# rf_router_swrmet.net
KiCad netlist of a schematic drawn in Altium Designer
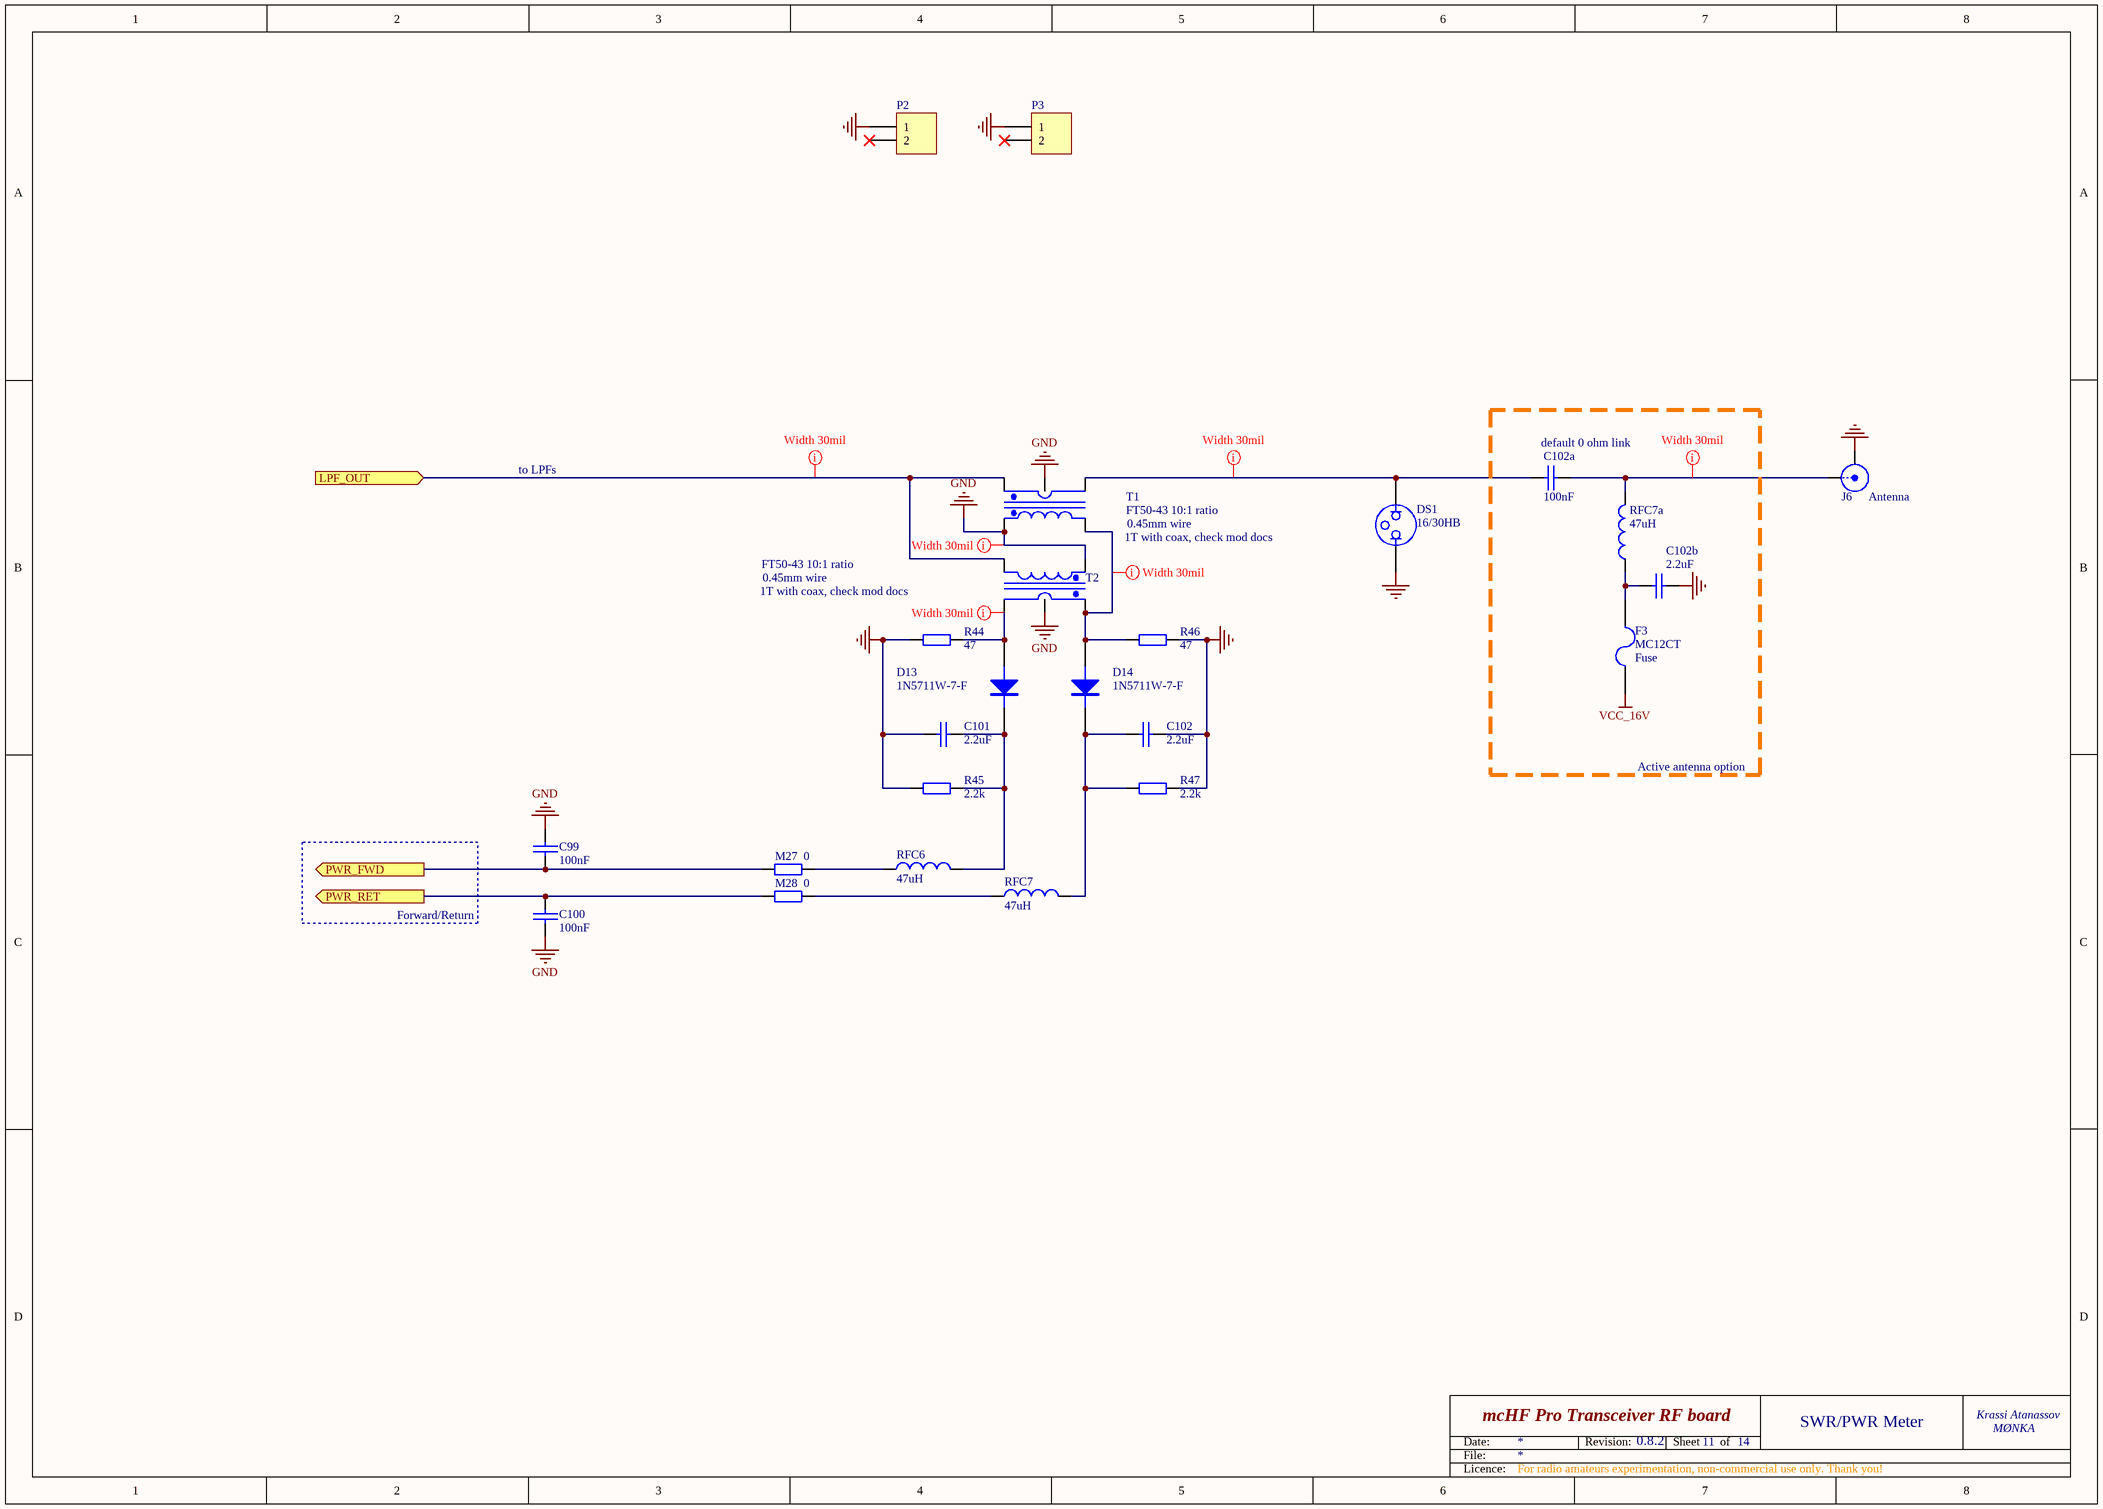
[diagram p0: rf_router_swrmet.SchDoc]

(export (version "E")
  (design (tool "Eeschema 10.0.6"))
  (components
    (comp (ref "C99")
      (value "100nF")
      (footprint "0805")
      (description "Capacitor")
      (libsource (lib "mcHF_rf") (part "CAP"))
    )
    (comp (ref "C100")
      (value "100nF")
      (footprint "0805")
      (description "Capacitor")
      (libsource (lib "mcHF_rf") (part "CAP"))
    )
    (comp (ref "C101")
      (value "2.2uF")
      (footprint "0805")
      (description "Capacitor")
      (libsource (lib "mcHF_rf") (part "CAP"))
    )
    (comp (ref "C102")
      (value "2.2uF")
      (footprint "0805")
      (description "Capacitor")
      (libsource (lib "mcHF_rf") (part "CAP"))
    )
    (comp (ref "C102a")
      (value "100nF")
      (footprint "0805")
      (description "Capacitor")
      (fields (field (name "VOLTAGE") "100V"))
      (libsource (lib "mcHF_rf") (part "CAP"))
    )
    (comp (ref "C102b")
      (value "2.2uF")
      (footprint "0805")
      (description "Capacitor")
      (libsource (lib "mcHF_rf") (part "CAP"))
    )
    (comp (ref "D13")
      (value "1N5711W-7-F")
      (footprint "SOD87")
      (description "RF DIODE SCHOTTKY 70V, SOD-123F")
      (libsource (lib "mcHF_rf") (part "PMEG6010CEH"))
    )
    (comp (ref "D14")
      (value "1N5711W-7-F")
      (footprint "SOD87")
      (description "RF DIODE SCHOTTKY 70V, SOD-123F")
      (libsource (lib "mcHF_rf") (part "PMEG6010CEH"))
    )
    (comp (ref "DS1")
      (value "16/30HB")
      (footprint "NEON")
      (description "NEON LAMP, WIRE ENDED, T2")
      (libsource (lib "__rf") (part "16/30HB"))
    )
    (comp (ref "F3")
      (value "MC12CT")
      (footprint "1206")
      (description "Fuse")
      (fields (field (name "FUNCTION") "Fuse"))
      (libsource (lib "mcHF_rf") (part "Fuse"))
    )
    (comp (ref "J6")
      (value "Antenna")
      (footprint "BNC_RA CON")
      (description "RF COAXIAL, BNC, JACK")
      (libsource (lib "mcHF_rf") (part "BNC"))
    )
    (comp (ref "M27")
      (value "0")
      (footprint "0805")
      (description "Resistor")
      (libsource (lib "") (part "RES_1"))
    )
    (comp (ref "M28")
      (value "0")
      (footprint "0805")
      (description "Resistor")
      (libsource (lib "") (part "RES_1"))
    )
    (comp (ref "P2")
      (value "Header 2")
      (footprint "SIP2")
      (description "Header, 2-Pin")
      (libsource (lib "__ui") (part "Header 2"))
    )
    (comp (ref "P3")
      (value "Header 2")
      (footprint "SIP2")
      (description "Header, 2-Pin")
      (libsource (lib "__ui") (part "Header 2"))
    )
    (comp (ref "R44")
      (value "47")
      (footprint "0805")
      (description "Resistor")
      (libsource (lib "mcHF_rf") (part "RES"))
    )
    (comp (ref "R45")
      (value "2.2k")
      (footprint "0805")
      (description "Resistor")
      (libsource (lib "mcHF_rf") (part "RES"))
    )
    (comp (ref "R46")
      (value "47")
      (footprint "0805")
      (description "Resistor")
      (libsource (lib "mcHF_rf") (part "RES"))
    )
    (comp (ref "R47")
      (value "2.2k")
      (footprint "0805")
      (description "Resistor")
      (libsource (lib "mcHF_rf") (part "RES"))
    )
    (comp (ref "RFC6")
      (value "47uH")
      (footprint "0805")
      (description "INDUCTOR, SIGNAL LINE, 47UH, 1005")
      (libsource (lib "mcHF_rf") (part "TDK-NLV25T"))
    )
    (comp (ref "RFC7")
      (value "47uH")
      (footprint "0805")
      (description "INDUCTOR, SIGNAL LINE, 47UH, 1005")
      (libsource (lib "mcHF_rf") (part "TDK-NLV25T"))
    )
    (comp (ref "RFC7a")
      (value "47uH")
      (footprint "0805")
      (description "INDUCTOR, SIGNAL LINE, 47UH, 1005")
      (libsource (lib "mcHF_rf") (part "TDK-NLV25T"))
    )
    (comp (ref "T1")
      (value "FT50-43 10:1 ratio")
      (footprint "SWR_TR _new")
      (description "SWR Bridge transformer")
      (libsource (lib "mcHF_rf") (part "SWR_TR"))
    )
    (comp (ref "T2")
      (value "FT50-43 10:1 ratio")
      (footprint "SWR_TR _new")
      (description "SWR Bridge transformer")
      (libsource (lib "mcHF_rf") (part "SWR_TR"))
    )
  )
  (nets
    (net (code "1") (name "/LPF_OUT") (class "Default")
      (node (ref "T1") (pin "3") (pinfunction "Sec+_3") (pintype "passive"))
      (node (ref "T2") (pin "2") (pinfunction "Pri-_2") (pintype "passive"))
    )
    (net (code "2") (name "/PWR_FWD") (class "Default")
      (node (ref "C99") (pin "2") (pinfunction "2_2") (pintype "passive"))
      (node (ref "M27") (pin "2") (pinfunction "2_2") (pintype "passive"))
    )
    (net (code "3") (name "/PWR_RET") (class "Default")
      (node (ref "C100") (pin "1") (pinfunction "1_1") (pintype "passive"))
      (node (ref "M28") (pin "2") (pinfunction "2_2") (pintype "passive"))
    )
    (net (code "4") (name "GND") (class "Default")
      (node (ref "C100") (pin "2") (pinfunction "2_2") (pintype "passive"))
      (node (ref "C101") (pin "1") (pinfunction "1_1") (pintype "passive"))
      (node (ref "C102") (pin "2") (pinfunction "2_2") (pintype "passive"))
      (node (ref "C102b") (pin "2") (pinfunction "2_2") (pintype "passive"))
      (node (ref "C99") (pin "1") (pinfunction "1_1") (pintype "passive"))
      (node (ref "DS1") (pin "1") (pinfunction "1_1") (pintype "passive"))
      (node (ref "J6") (pin "2") (pinfunction "Y_2") (pintype "passive"))
      (node (ref "P2") (pin "1") (pinfunction "1_1") (pintype "passive"))
      (node (ref "P3") (pin "1") (pinfunction "1_1") (pintype "passive"))
      (node (ref "R44") (pin "1") (pinfunction "1_1") (pintype "passive"))
      (node (ref "R45") (pin "1") (pinfunction "1_1") (pintype "passive"))
      (node (ref "R46") (pin "2") (pinfunction "2_2") (pintype "passive"))
      (node (ref "R47") (pin "2") (pinfunction "2_2") (pintype "passive"))
      (node (ref "T1") (pin "1") (pinfunction "Pri+_1") (pintype "passive"))
      (node (ref "T1") (pin "5") (pinfunction "Shield_5") (pintype "passive"))
      (node (ref "T2") (pin "1") (pinfunction "Pri+_1") (pintype "passive"))
      (node (ref "T2") (pin "5") (pinfunction "Shield_5") (pintype "passive"))
    )
    (net (code "5") (name "Net-(C102b-Pad1)") (class "Default")
      (node (ref "C102b") (pin "1") (pinfunction "1_1") (pintype "passive"))
      (node (ref "F3") (pin "1") (pinfunction "1_1") (pintype "passive"))
      (node (ref "RFC7a") (pin "1") (pinfunction "1_1") (pintype "passive"))
    )
    (net (code "6") (name "Net-(D13-A)") (class "Default")
      (node (ref "D13") (pin "1") (pinfunction "A_1") (pintype "passive"))
      (node (ref "R44") (pin "2") (pinfunction "2_2") (pintype "passive"))
      (node (ref "T2") (pin "4") (pinfunction "Sec-_4") (pintype "passive"))
    )
    (net (code "7") (name "Net-(D13-K)") (class "Default")
      (node (ref "C101") (pin "2") (pinfunction "2_2") (pintype "passive"))
      (node (ref "D13") (pin "2") (pinfunction "K_2") (pintype "passive"))
      (node (ref "R45") (pin "2") (pinfunction "2_2") (pintype "passive"))
      (node (ref "RFC6") (pin "2") (pinfunction "2_2") (pintype "passive"))
    )
    (net (code "8") (name "Net-(D14-A)") (class "Default")
      (node (ref "D14") (pin "1") (pinfunction "A_1") (pintype "passive"))
      (node (ref "R46") (pin "1") (pinfunction "1_1") (pintype "passive"))
      (node (ref "T1") (pin "2") (pinfunction "Pri-_2") (pintype "passive"))
      (node (ref "T2") (pin "3") (pinfunction "Sec+_3") (pintype "passive"))
    )
    (net (code "9") (name "Net-(D14-K)") (class "Default")
      (node (ref "C102") (pin "1") (pinfunction "1_1") (pintype "passive"))
      (node (ref "D14") (pin "2") (pinfunction "K_2") (pintype "passive"))
      (node (ref "R47") (pin "1") (pinfunction "1_1") (pintype "passive"))
      (node (ref "RFC7") (pin "2") (pinfunction "2_2") (pintype "passive"))
    )
    (net (code "10") (name "Net-(J6-X)") (class "Default")
      (node (ref "C102a") (pin "1") (pinfunction "1_1") (pintype "passive"))
      (node (ref "J6") (pin "1") (pinfunction "X_1") (pintype "passive"))
      (node (ref "RFC7a") (pin "2") (pinfunction "2_2") (pintype "passive"))
    )
    (net (code "11") (name "Net-(M27-Pad1)") (class "Default")
      (node (ref "M27") (pin "1") (pinfunction "1_1") (pintype "passive"))
      (node (ref "RFC6") (pin "1") (pinfunction "1_1") (pintype "passive"))
    )
    (net (code "12") (name "Net-(M28-Pad1)") (class "Default")
      (node (ref "M28") (pin "1") (pinfunction "1_1") (pintype "passive"))
      (node (ref "RFC7") (pin "1") (pinfunction "1_1") (pintype "passive"))
    )
    (net (code "13") (name "Net-(T1-Sec-)") (class "Default")
      (node (ref "C102a") (pin "2") (pinfunction "2_2") (pintype "passive"))
      (node (ref "DS1") (pin "2") (pinfunction "2_2") (pintype "passive"))
      (node (ref "T1") (pin "4") (pinfunction "Sec-_4") (pintype "passive"))
    )
    (net (code "14") (name "VCC_16V") (class "Default")
      (node (ref "F3") (pin "2") (pinfunction "2_2") (pintype "passive"))
    )
    (net (code "15") (name "unconnected-(P2-Pad2)") (class "Default")
      (node (ref "P2") (pin "2") (pinfunction "2_2") (pintype "passive+no_connect"))
    )
    (net (code "16") (name "unconnected-(P3-Pad2)") (class "Default")
      (node (ref "P3") (pin "2") (pinfunction "2_2") (pintype "passive+no_connect"))
    )
  )
)
